# HAM-VL_V1_5.net
KiCad netlist of a schematic drawn in EasyEDA
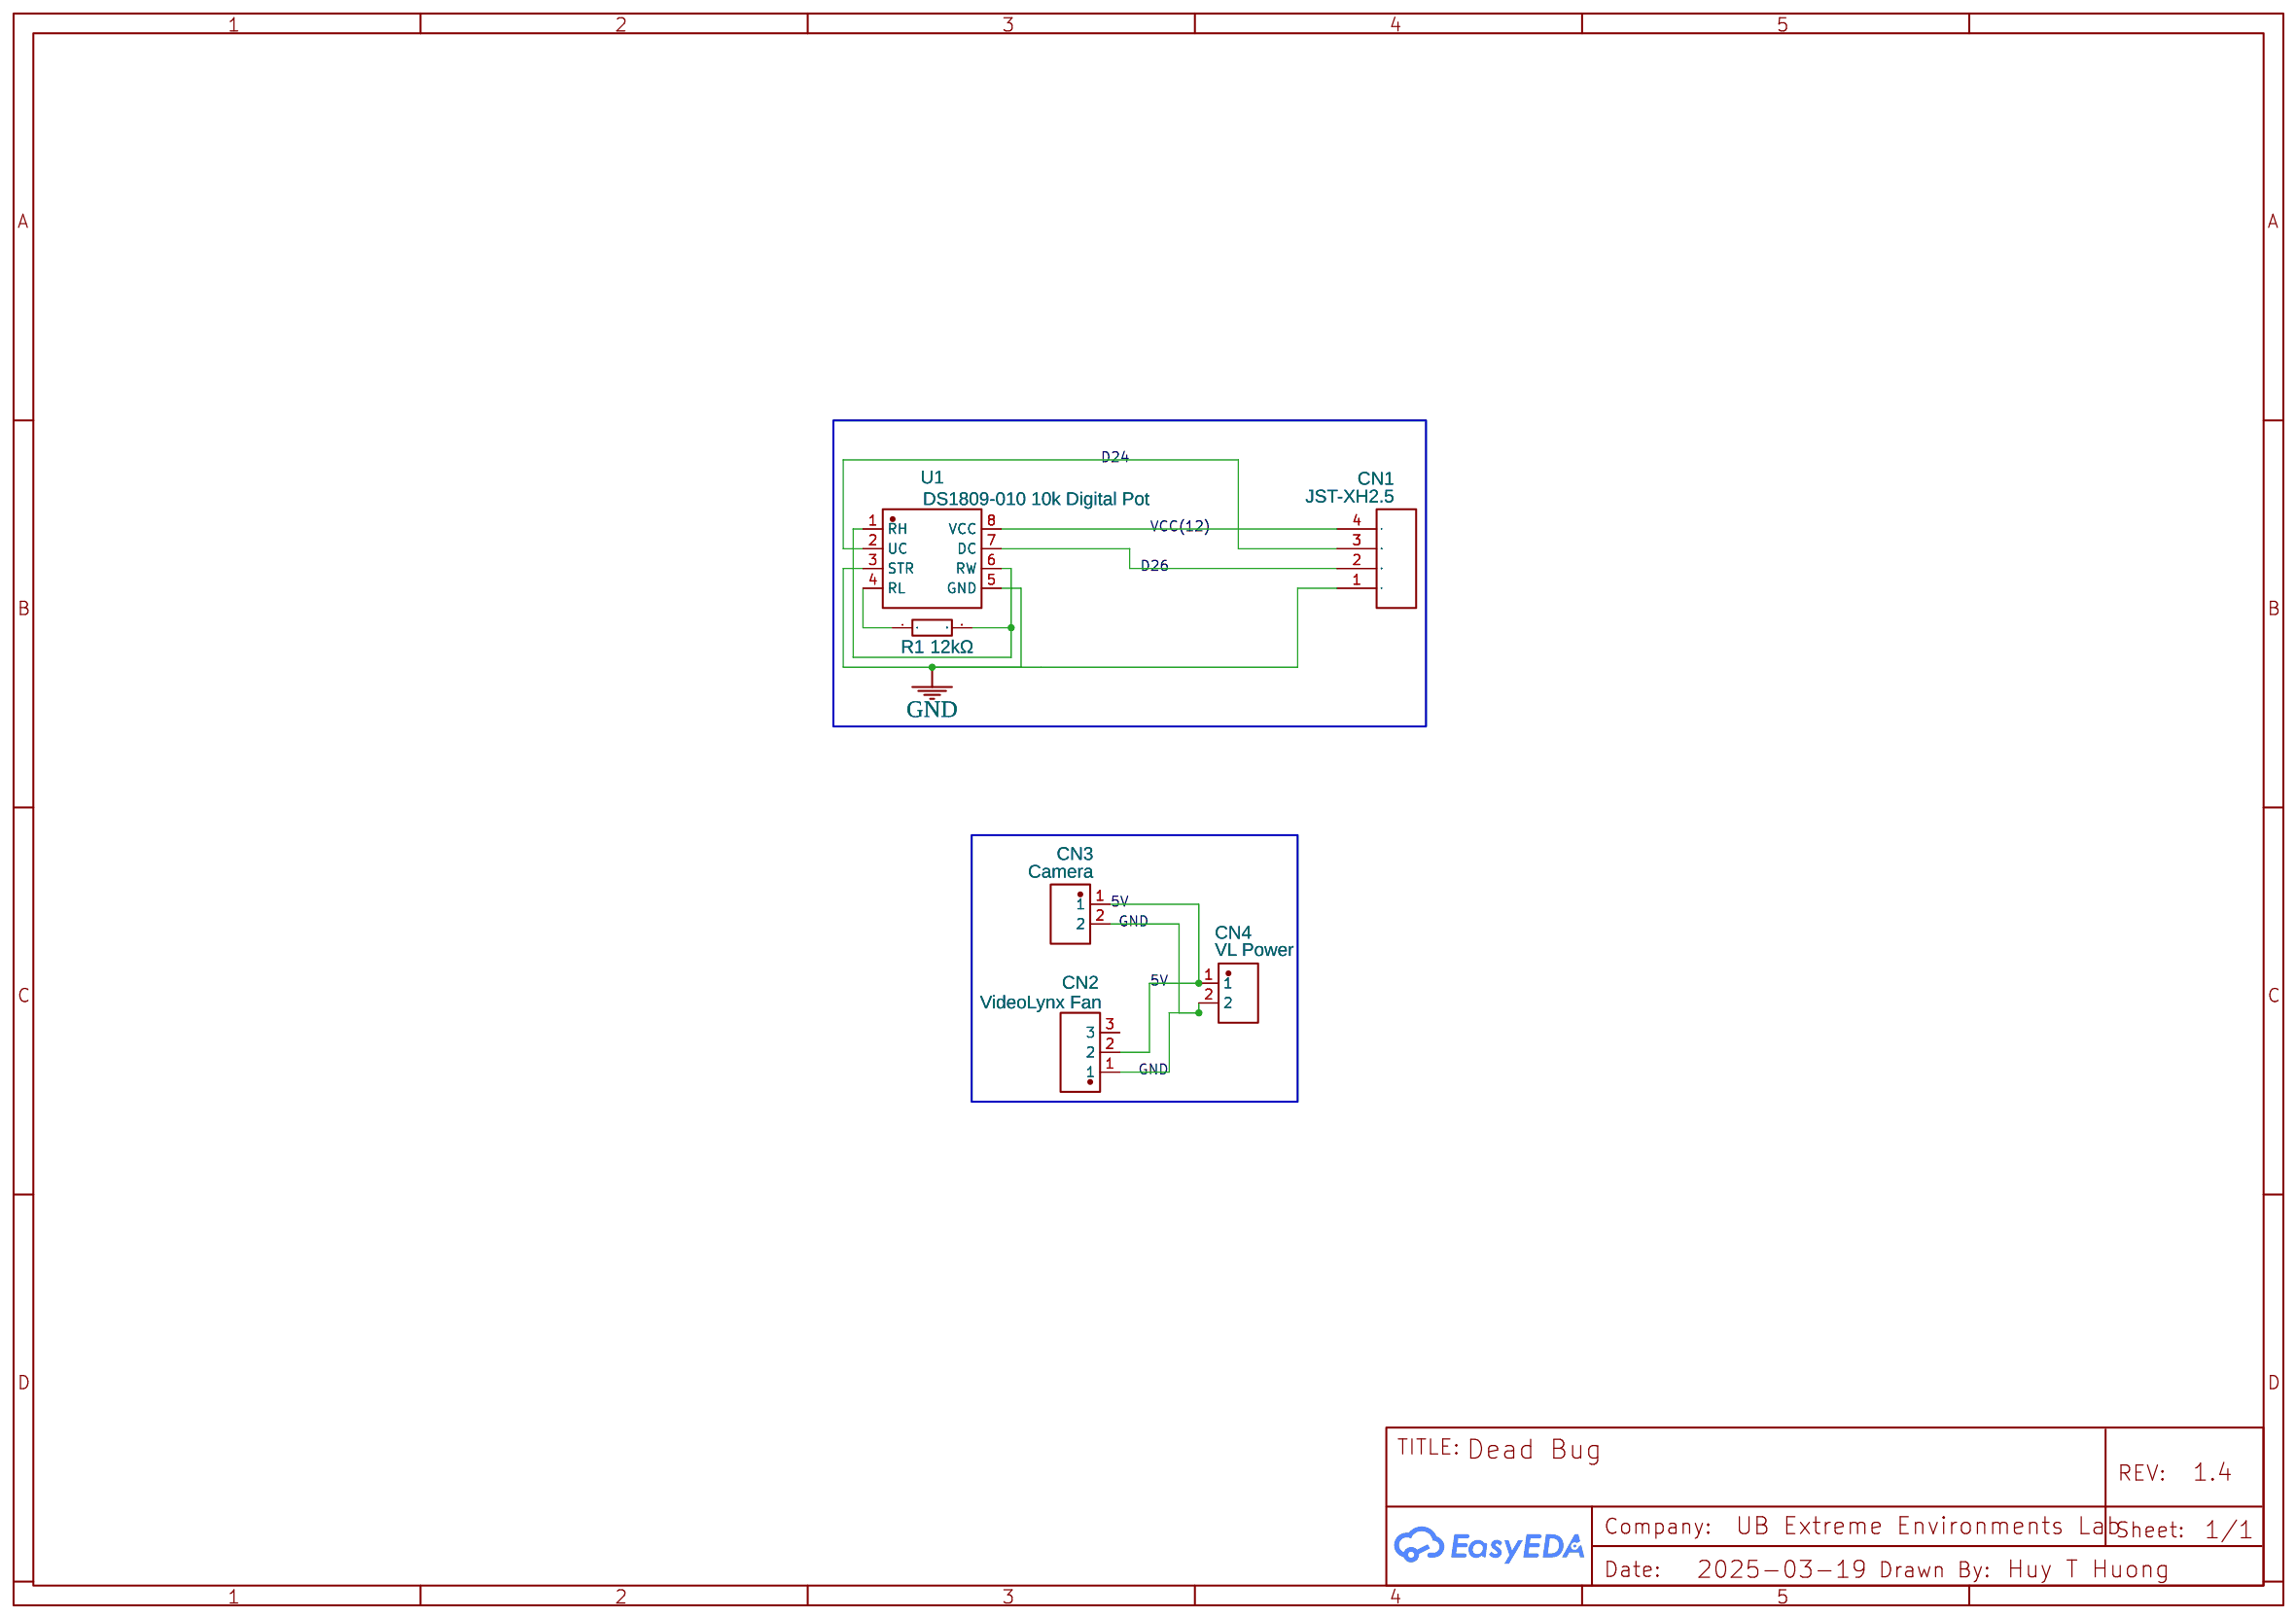
[diagram p0: schematic sheet]

(export (version "E")
  (design (tool "Eeschema 10.0.6"))
  (components
    (comp (ref "CN1") (value "JST-XH2.5") (libsource (lib "") (part "JST-XH2.54- 4 PIN Y COPY")))
    (comp (ref "CN2")
      (value "VideoLynx Fan")
      (fields (field (name "Manufacturer Part") "XH插座1*3P间距2.5mm直针,"))
      (libsource (lib "") (part "XH插座1*3P间距2.5MM直针,"))
    )
    (comp (ref "CN3")
      (value "Camera")
      (fields (field (name "Manufacturer Part") "XH-2P-2.54"))
      (libsource (lib "") (part "XH-2P-2.54_1"))
    )
    (comp (ref "CN4")
      (value "VL Power")
      (fields (field (name "Manufacturer Part") "XH-2P-2.54"))
      (libsource (lib "") (part "XH-2P-2.54"))
    )
    (comp (ref "R1")
      (value "12kΩ")
      (fields (field (name "Manufacturer Part") "MFR-25FTE52-12K") (field (name "Manufacturer") "YAGEO(国巨)"))
      (libsource (lib "") (part "MFR-25FTE52-12K"))
    )
    (comp (ref "U1")
      (value "DS1809-010 10k Digital Pot")
      (fields
        (field (name "Manufacturer Part") "DS1809-010+")
        (field (name "Manufacturer") "ADI(亚德诺)/MAXIM(美信)")
      )
      (libsource (lib "") (part "DS1809-010+"))
    )
  )
  (nets
    (net (code "1") (name "/5V") (class "Default")
      (node (ref "CN2") (pin "2") (pinfunction "2_2") (pintype "unspecified"))
      (node (ref "CN3") (pin "1") (pinfunction "1_1") (pintype "unspecified"))
      (node (ref "CN4") (pin "1") (pinfunction "1_1") (pintype "unspecified"))
    )
    (net (code "2") (name "/D24") (class "Default")
      (node (ref "CN1") (pin "3") (pinfunction "3_3") (pintype "unspecified"))
      (node (ref "U1") (pin "2") (pinfunction "UC_2") (pintype "unspecified"))
    )
    (net (code "3") (name "/D26") (class "Default")
      (node (ref "CN1") (pin "2") (pinfunction "2_2") (pintype "unspecified"))
      (node (ref "U1") (pin "7") (pinfunction "DC_7") (pintype "unspecified"))
    )
    (net (code "4") (name "/VCC(12)") (class "Default")
      (node (ref "CN1") (pin "4") (pinfunction "4_4") (pintype "unspecified"))
      (node (ref "U1") (pin "8") (pinfunction "VCC_8") (pintype "unspecified"))
    )
    (net (code "5") (name "GND") (class "Default")
      (node (ref "CN1") (pin "1") (pinfunction "1_1") (pintype "unspecified"))
      (node (ref "CN2") (pin "1") (pinfunction "1_1") (pintype "unspecified"))
      (node (ref "CN3") (pin "2") (pinfunction "2_2") (pintype "unspecified"))
      (node (ref "CN4") (pin "2") (pinfunction "2_2") (pintype "unspecified"))
      (node (ref "U1") (pin "3") (pinfunction "STR_3") (pintype "unspecified"))
      (node (ref "U1") (pin "5") (pinfunction "GND_5") (pintype "unspecified"))
    )
    (net (code "6") (name "Net-(U1-RH)") (class "Default")
      (node (ref "R1") (pin "2") (pinfunction "2_2") (pintype "input"))
      (node (ref "U1") (pin "1") (pinfunction "RH_1") (pintype "unspecified"))
      (node (ref "U1") (pin "6") (pinfunction "RW_6") (pintype "unspecified"))
    )
    (net (code "7") (name "Net-(U1-RL)") (class "Default")
      (node (ref "R1") (pin "1") (pinfunction "1_1") (pintype "input"))
      (node (ref "U1") (pin "4") (pinfunction "RL_4") (pintype "unspecified"))
    )
    (net (code "8") (name "unconnected-(CN2-Pad3)") (class "Default")
      (node (ref "CN2") (pin "3") (pinfunction "3_3") (pintype "unspecified"))
    )
  )
)
